# biv2-LRTP_1a.net
KiCad netlist of a schematic drawn in Altium Designer
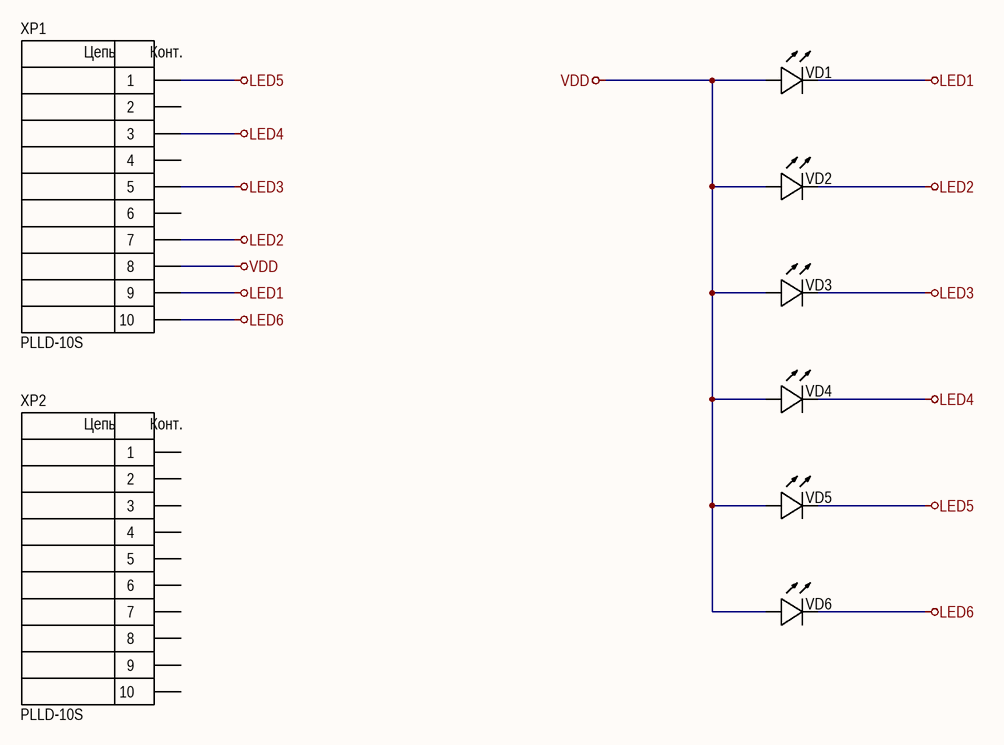
[diagram p0: biv2-LRTP_1a.SchDoc]

(export (version "E")
  (design (tool "Eeschema 10.0.6"))
  (components
    (comp (ref "VD1")
      (value "KM2520SURCK09")
      (footprint "KM2520SURCK09")
      (description "LED")
      (libsource (lib "Kingbright LED") (part "KM2520SURCK09"))
    )
    (comp (ref "VD2")
      (value "KM2520SURCK09")
      (footprint "KM2520SURCK09")
      (description "LED")
      (libsource (lib "Kingbright LED") (part "KM2520SURCK09"))
    )
    (comp (ref "VD3")
      (value "KM2520SURCK09")
      (footprint "KM2520SURCK09")
      (description "LED")
      (libsource (lib "Kingbright LED") (part "KM2520SURCK09"))
    )
    (comp (ref "VD4")
      (value "KM2520SURCK09")
      (footprint "KM2520SURCK09")
      (description "LED")
      (libsource (lib "Kingbright LED") (part "KM2520SURCK09"))
    )
    (comp (ref "VD5")
      (value "KM2520SURCK09")
      (footprint "KM2520SURCK09")
      (description "LED")
      (libsource (lib "Kingbright LED") (part "KM2520SURCK09"))
    )
    (comp (ref "VD6")
      (value "KM2520SURCK09")
      (footprint "KM2520SURCK09")
      (description "LED")
      (libsource (lib "Kingbright LED") (part "KM2520SURCK09"))
    )
    (comp (ref "XP1")
      (value "PLLD-10S")
      (footprint "CON: PLLD-10S")
      (description "Step 1.27")
      (libsource (lib "connector") (part "PLLD-10S"))
    )
    (comp (ref "XP2")
      (value "PLLD-10S")
      (footprint "CON: PLLD-10S")
      (description "Step 1.27")
      (libsource (lib "connector") (part "PLLD-10S"))
    )
  )
  (nets
    (net (code "1") (name "LED1") (class "Default")
      (node (ref "VD1") (pin "2") (pinfunction "K_2") (pintype "passive"))
      (node (ref "XP1") (pin "9") (pinfunction "9_9") (pintype "passive"))
    )
    (net (code "2") (name "LED2") (class "Default")
      (node (ref "VD2") (pin "2") (pinfunction "K_2") (pintype "passive"))
      (node (ref "XP1") (pin "7") (pinfunction "7_7") (pintype "passive"))
    )
    (net (code "3") (name "LED3") (class "Default")
      (node (ref "VD3") (pin "2") (pinfunction "K_2") (pintype "passive"))
      (node (ref "XP1") (pin "5") (pinfunction "5_5") (pintype "passive"))
    )
    (net (code "4") (name "LED4") (class "Default")
      (node (ref "VD4") (pin "2") (pinfunction "K_2") (pintype "passive"))
      (node (ref "XP1") (pin "3") (pinfunction "3_3") (pintype "passive"))
    )
    (net (code "5") (name "LED5") (class "Default")
      (node (ref "VD5") (pin "2") (pinfunction "K_2") (pintype "passive"))
      (node (ref "XP1") (pin "1") (pinfunction "1_1") (pintype "passive"))
    )
    (net (code "6") (name "LED6") (class "Default")
      (node (ref "VD6") (pin "2") (pinfunction "K_2") (pintype "passive"))
      (node (ref "XP1") (pin "10") (pinfunction "10_10") (pintype "passive"))
    )
    (net (code "7") (name "VDD") (class "Default")
      (node (ref "VD1") (pin "1") (pinfunction "A_1") (pintype "passive"))
      (node (ref "VD2") (pin "1") (pinfunction "A_1") (pintype "passive"))
      (node (ref "VD3") (pin "1") (pinfunction "A_1") (pintype "passive"))
      (node (ref "VD4") (pin "1") (pinfunction "A_1") (pintype "passive"))
      (node (ref "VD5") (pin "1") (pinfunction "A_1") (pintype "passive"))
      (node (ref "VD6") (pin "1") (pinfunction "A_1") (pintype "passive"))
      (node (ref "XP1") (pin "8") (pinfunction "8_8") (pintype "passive"))
    )
    (net (code "8") (name "unconnected-(XP1-Pad2)") (class "Default")
      (node (ref "XP1") (pin "2") (pinfunction "2_2") (pintype "passive"))
    )
    (net (code "9") (name "unconnected-(XP1-Pad4)") (class "Default")
      (node (ref "XP1") (pin "4") (pinfunction "4_4") (pintype "passive"))
    )
    (net (code "10") (name "unconnected-(XP1-Pad6)") (class "Default")
      (node (ref "XP1") (pin "6") (pinfunction "6_6") (pintype "passive"))
    )
    (net (code "11") (name "unconnected-(XP2-Pad1)") (class "Default")
      (node (ref "XP2") (pin "1") (pinfunction "1_1") (pintype "passive"))
    )
    (net (code "12") (name "unconnected-(XP2-Pad2)") (class "Default")
      (node (ref "XP2") (pin "2") (pinfunction "2_2") (pintype "passive"))
    )
    (net (code "13") (name "unconnected-(XP2-Pad3)") (class "Default")
      (node (ref "XP2") (pin "3") (pinfunction "3_3") (pintype "passive"))
    )
    (net (code "14") (name "unconnected-(XP2-Pad4)") (class "Default")
      (node (ref "XP2") (pin "4") (pinfunction "4_4") (pintype "passive"))
    )
    (net (code "15") (name "unconnected-(XP2-Pad5)") (class "Default")
      (node (ref "XP2") (pin "5") (pinfunction "5_5") (pintype "passive"))
    )
    (net (code "16") (name "unconnected-(XP2-Pad6)") (class "Default")
      (node (ref "XP2") (pin "6") (pinfunction "6_6") (pintype "passive"))
    )
    (net (code "17") (name "unconnected-(XP2-Pad7)") (class "Default")
      (node (ref "XP2") (pin "7") (pinfunction "7_7") (pintype "passive"))
    )
    (net (code "18") (name "unconnected-(XP2-Pad8)") (class "Default")
      (node (ref "XP2") (pin "8") (pinfunction "8_8") (pintype "passive"))
    )
    (net (code "19") (name "unconnected-(XP2-Pad9)") (class "Default")
      (node (ref "XP2") (pin "9") (pinfunction "9_9") (pintype "passive"))
    )
    (net (code "20") (name "unconnected-(XP2-Pad10)") (class "Default")
      (node (ref "XP2") (pin "10") (pinfunction "10_10") (pintype "passive"))
    )
  )
)
